# ATtiny85_and_DRV8830_Combo_--_v03.net
KiCad netlist of a schematic drawn in EAGLE
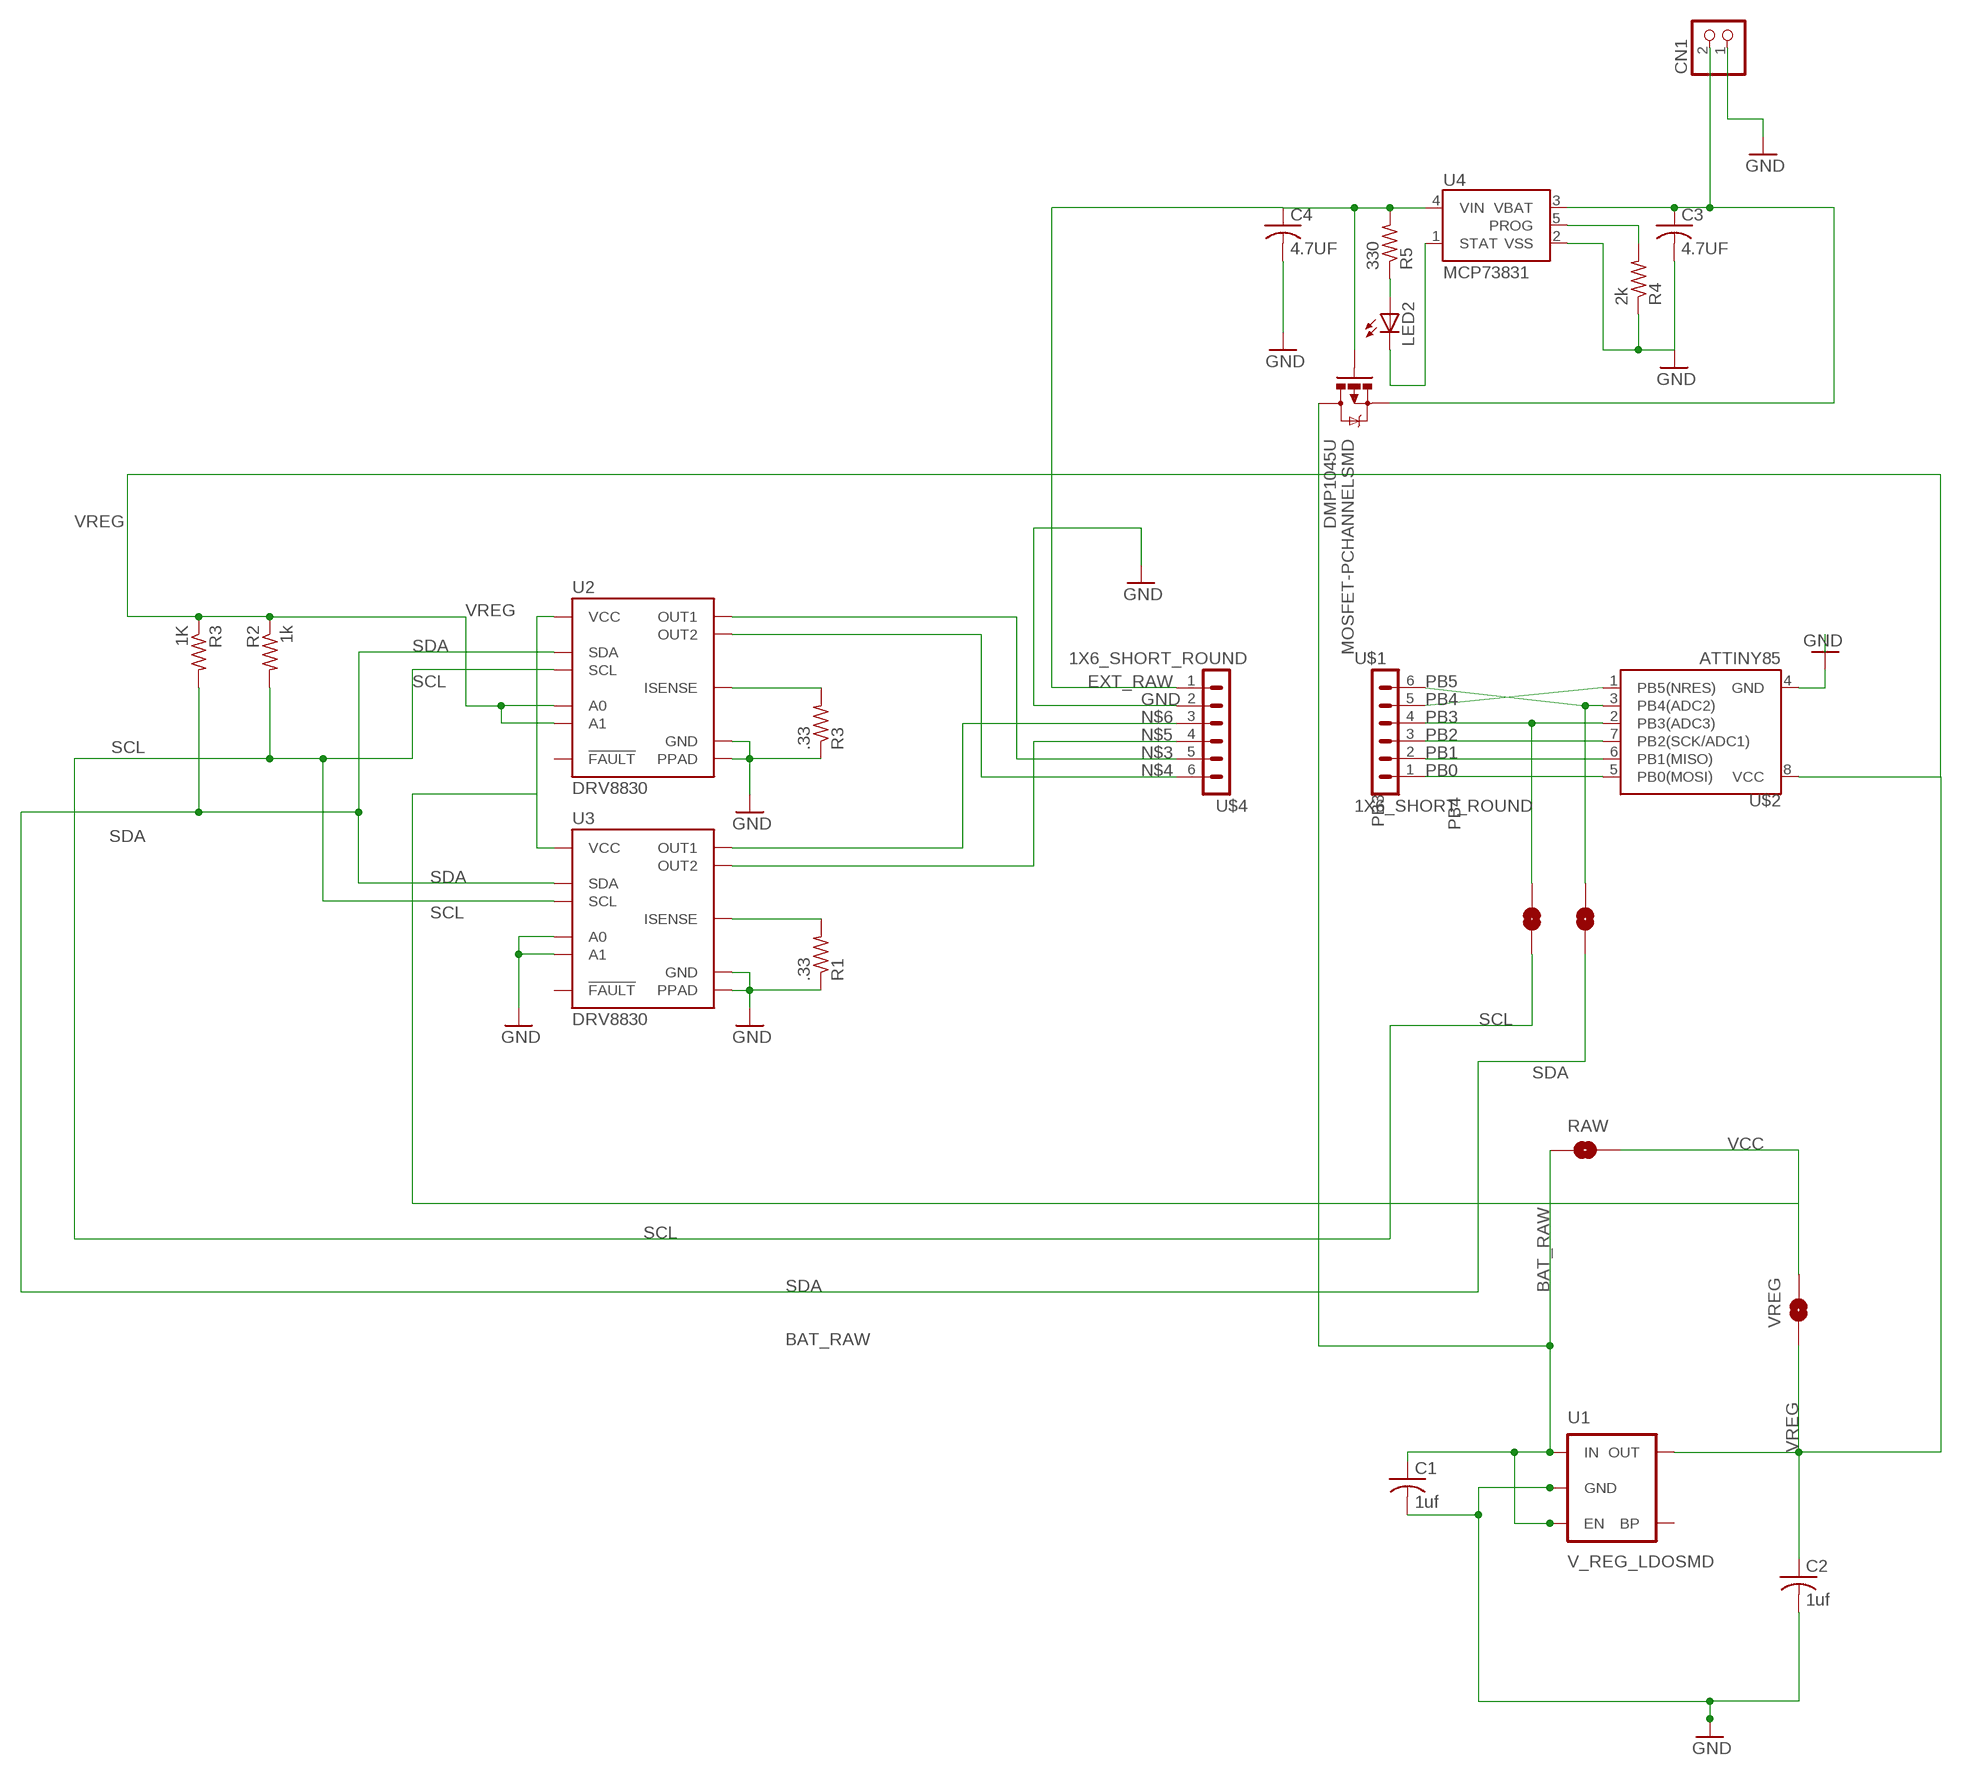
[diagram p0: schematic, sheet 1]

(export (version "E")
  (design (tool "Eeschema 10.0.6"))
  (components
    (comp (ref "1K")
      (value "R3")
      (footprint "eagle-import:R0402")
      (libsource (lib "eagle-import") (part "R-US_R0402"))
    )
    (comp (ref "C1")
      (value "1uf")
      (footprint "eagle-import:C0402")
      (libsource (lib "eagle-import") (part "C-USC0402"))
    )
    (comp (ref "C2")
      (value "1uf")
      (footprint "eagle-import:C0402")
      (libsource (lib "eagle-import") (part "C-USC0402"))
    )
    (comp (ref "C3")
      (value "4.7UF")
      (footprint "eagle-import:C0805K")
      (libsource (lib "eagle-import") (part "C-USC0805K"))
    )
    (comp (ref "C4")
      (value "4.7UF")
      (footprint "eagle-import:C0805K")
      (libsource (lib "eagle-import") (part "C-USC0805K"))
    )
    (comp (ref "CN1")
      (value "JST_2PIN-THM")
      (footprint "eagle-import:JST-PH-2-THM")
      (libsource (lib "eagle-import") (part "JST_2PIN-THM"))
    )
    (comp (ref "DMP1045U")
      (value "MOSFET-PCHANNELSMD")
      (footprint "eagle-import:SOT23-3")
      (libsource (lib "eagle-import") (part "MOSFET-PCHANNELSMD"))
    )
    (comp (ref "LED2")
      (value "LEDSML0603")
      (footprint "eagle-import:SML0603")
      (libsource (lib "eagle-import") (part "LEDSML0603"))
    )
    (comp (ref "R1")
      (value ".33")
      (footprint "eagle-import:R0402")
      (libsource (lib "eagle-import") (part "R-US_R0402"))
    )
    (comp (ref "R2")
      (value "1k")
      (footprint "eagle-import:R0402")
      (libsource (lib "eagle-import") (part "R-US_R0402"))
    )
    (comp (ref "R3")
      (value ".33")
      (footprint "eagle-import:R0402")
      (libsource (lib "eagle-import") (part "R-US_R0402"))
    )
    (comp (ref "R4")
      (value "2k")
      (footprint "eagle-import:R0402")
      (libsource (lib "eagle-import") (part "R-US_R0402"))
    )
    (comp (ref "R5")
      (value "330")
      (footprint "eagle-import:R0402")
      (libsource (lib "eagle-import") (part "R-US_R0402"))
    )
    (comp (ref "RAW")
      (value "SOLDERJUMPERNO")
      (footprint "eagle-import:SJ_2S-NO")
      (libsource (lib "eagle-import") (part "SOLDERJUMPERNO"))
    )
    (comp (ref "SJ6")
      (value "SOLDERJUMPERNO")
      (footprint "eagle-import:SJ_2S-NO")
      (libsource (lib "eagle-import") (part "SOLDERJUMPERNO"))
    )
    (comp (ref "SJ7")
      (value "SOLDERJUMPERNO")
      (footprint "eagle-import:SJ_2S-NO")
      (libsource (lib "eagle-import") (part "SOLDERJUMPERNO"))
    )
    (comp (ref "U$1")
      (value "1X6_SHORT_ROUND")
      (footprint "eagle-import:1X6_SHORT_ROUND")
      (libsource (lib "eagle-import") (part "1X6_SHORT_ROUND"))
    )
    (comp (ref "U$2")
      (value "ATTINY85")
      (footprint "eagle-import:SO08-EIAJ")
      (libsource (lib "eagle-import") (part "ATTINY45"))
    )
    (comp (ref "U$4")
      (value "1X6_SHORT_ROUND")
      (footprint "eagle-import:1X6_SHORT_ROUND")
      (libsource (lib "eagle-import") (part "1X6_SHORT_ROUND"))
    )
    (comp (ref "U1")
      (value "V_REG_LDOSMD")
      (footprint "eagle-import:SOT23-5")
      (libsource (lib "eagle-import") (part "V_REG_LDOSMD"))
    )
    (comp (ref "U2")
      (value "DRV8830")
      (footprint "eagle-import:MSOP-10-GNDPAD")
      (libsource (lib "eagle-import") (part "DRV8830"))
    )
    (comp (ref "U3")
      (value "DRV8830")
      (footprint "eagle-import:MSOP-10-GNDPAD")
      (libsource (lib "eagle-import") (part "DRV8830"))
    )
    (comp (ref "U4")
      (value "MCP73831")
      (footprint "eagle-import:SOT23-5")
      (libsource (lib "eagle-import") (part "MCP73831"))
    )
    (comp (ref "VREG")
      (value "SOLDERJUMPERNO")
      (footprint "eagle-import:SJ_2S-NO")
      (libsource (lib "eagle-import") (part "SOLDERJUMPERNO"))
    )
  )
  (nets
    (net (code "1") (name "/BAT_RAW") (class "Default")
      (node (ref "C1") (pin "1") (pinfunction "1_1") (pintype "passive"))
      (node (ref "DMP1045U") (pin "3") (pinfunction "D_3") (pintype "passive"))
      (node (ref "RAW") (pin "1") (pinfunction "1_1") (pintype "passive"))
      (node (ref "U1") (pin "1") (pinfunction "IN_1") (pintype "input"))
      (node (ref "U1") (pin "3") (pinfunction "EN_3") (pintype "input"))
    )
    (net (code "2") (name "/EXT_RAW") (class "Default")
      (node (ref "C4") (pin "1") (pinfunction "1_1") (pintype "passive"))
      (node (ref "DMP1045U") (pin "1") (pinfunction "G_1") (pintype "passive"))
      (node (ref "R5") (pin "2") (pinfunction "2_2") (pintype "passive"))
      (node (ref "U$4") (pin "1") (pinfunction "1_1") (pintype "passive"))
      (node (ref "U4") (pin "4") (pinfunction "VIN_4") (pintype "power_in"))
    )
    (net (code "3") (name "/N$3") (class "Default")
      (node (ref "U$4") (pin "5") (pinfunction "5_5") (pintype "passive"))
      (node (ref "U2") (pin "3") (pinfunction "OUT1_3") (pintype "power_in"))
    )
    (net (code "4") (name "/N$4") (class "Default")
      (node (ref "U$4") (pin "6") (pinfunction "6_6") (pintype "passive"))
      (node (ref "U2") (pin "1") (pinfunction "OUT2_1") (pintype "power_in"))
    )
    (net (code "5") (name "/N$5") (class "Default")
      (node (ref "U$4") (pin "4") (pinfunction "4_4") (pintype "passive"))
      (node (ref "U3") (pin "1") (pinfunction "OUT2_1") (pintype "power_in"))
    )
    (net (code "6") (name "/N$6") (class "Default")
      (node (ref "U$4") (pin "3") (pinfunction "3_3") (pintype "passive"))
      (node (ref "U3") (pin "3") (pinfunction "OUT1_3") (pintype "power_in"))
    )
    (net (code "7") (name "/PB0") (class "Default")
      (node (ref "U$1") (pin "1") (pinfunction "1_1") (pintype "passive"))
      (node (ref "U$2") (pin "5") (pinfunction "PB0(MOSI)_5") (pintype "bidirectional"))
    )
    (net (code "8") (name "/PB1") (class "Default")
      (node (ref "U$1") (pin "2") (pinfunction "2_2") (pintype "passive"))
      (node (ref "U$2") (pin "6") (pinfunction "PB1(MISO)_6") (pintype "bidirectional"))
    )
    (net (code "9") (name "/PB2") (class "Default")
      (node (ref "U$1") (pin "3") (pinfunction "3_3") (pintype "passive"))
      (node (ref "U$2") (pin "7") (pinfunction "PB2(SCK/ADC1)_7") (pintype "bidirectional"))
    )
    (net (code "10") (name "/PB3") (class "Default")
      (node (ref "SJ7") (pin "2") (pinfunction "2_2") (pintype "passive"))
      (node (ref "U$1") (pin "4") (pinfunction "4_4") (pintype "passive"))
      (node (ref "U$2") (pin "2") (pinfunction "PB3(ADC3)_2") (pintype "bidirectional"))
    )
    (net (code "11") (name "/PB4") (class "Default")
      (node (ref "SJ6") (pin "2") (pinfunction "2_2") (pintype "passive"))
      (node (ref "U$1") (pin "6") (pinfunction "6_6") (pintype "passive"))
      (node (ref "U$2") (pin "3") (pinfunction "PB4(ADC2)_3") (pintype "bidirectional"))
    )
    (net (code "12") (name "/PB5") (class "Default")
      (node (ref "U$1") (pin "5") (pinfunction "5_5") (pintype "passive"))
      (node (ref "U$2") (pin "1") (pinfunction "PB5(NRES)_1") (pintype "bidirectional"))
    )
    (net (code "13") (name "/SCL") (class "Default")
      (node (ref "R2") (pin "2") (pinfunction "2_2") (pintype "passive"))
      (node (ref "SJ7") (pin "1") (pinfunction "1_1") (pintype "passive"))
      (node (ref "U2") (pin "10") (pinfunction "SCL_10") (pintype "input"))
      (node (ref "U3") (pin "10") (pinfunction "SCL_10") (pintype "input"))
    )
    (net (code "14") (name "/SDA") (class "Default")
      (node (ref "1K") (pin "2") (pinfunction "2_2") (pintype "passive"))
      (node (ref "SJ6") (pin "1") (pinfunction "1_1") (pintype "passive"))
      (node (ref "U2") (pin "9") (pinfunction "SDA_9") (pintype "bidirectional"))
      (node (ref "U3") (pin "9") (pinfunction "SDA_9") (pintype "bidirectional"))
    )
    (net (code "15") (name "/VCC") (class "Default")
      (node (ref "RAW") (pin "2") (pinfunction "2_2") (pintype "passive"))
      (node (ref "U2") (pin "4") (pinfunction "VCC_4") (pintype "power_in"))
      (node (ref "U3") (pin "4") (pinfunction "VCC_4") (pintype "power_in"))
      (node (ref "VREG") (pin "2") (pinfunction "2_2") (pintype "passive"))
    )
    (net (code "16") (name "/VREG") (class "Default")
      (node (ref "1K") (pin "1") (pinfunction "1_1") (pintype "passive"))
      (node (ref "C2") (pin "1") (pinfunction "1_1") (pintype "passive"))
      (node (ref "R2") (pin "1") (pinfunction "1_1") (pintype "passive"))
      (node (ref "U$2") (pin "8") (pinfunction "VCC_8") (pintype "bidirectional"))
      (node (ref "U1") (pin "5") (pinfunction "OUT_5") (pintype "passive"))
      (node (ref "U2") (pin "7") (pinfunction "A0_7") (pintype "input"))
      (node (ref "U2") (pin "8") (pinfunction "A1_8") (pintype "input"))
      (node (ref "VREG") (pin "1") (pinfunction "1_1") (pintype "passive"))
    )
    (net (code "17") (name "GND") (class "Default")
      (node (ref "C1") (pin "2") (pinfunction "2_2") (pintype "passive"))
      (node (ref "C2") (pin "2") (pinfunction "2_2") (pintype "passive"))
      (node (ref "C3") (pin "2") (pinfunction "2_2") (pintype "passive"))
      (node (ref "C4") (pin "2") (pinfunction "2_2") (pintype "passive"))
      (node (ref "CN1") (pin "1") (pinfunction "2_1") (pintype "passive"))
      (node (ref "R1") (pin "1") (pinfunction "1_1") (pintype "passive"))
      (node (ref "R3") (pin "1") (pinfunction "1_1") (pintype "passive"))
      (node (ref "R4") (pin "1") (pinfunction "1_1") (pintype "passive"))
      (node (ref "U$2") (pin "4") (pinfunction "GND_4") (pintype "bidirectional"))
      (node (ref "U$4") (pin "2") (pinfunction "2_2") (pintype "passive"))
      (node (ref "U1") (pin "2") (pinfunction "GND_2") (pintype "input"))
      (node (ref "U2") (pin "5") (pinfunction "GND_5") (pintype "power_in"))
      (node (ref "U2") (pin "GND") (pinfunction "PPAD_GND") (pintype "power_in"))
      (node (ref "U3") (pin "5") (pinfunction "GND_5") (pintype "power_in"))
      (node (ref "U3") (pin "7") (pinfunction "A0_7") (pintype "input"))
      (node (ref "U3") (pin "8") (pinfunction "A1_8") (pintype "input"))
      (node (ref "U3") (pin "GND") (pinfunction "PPAD_GND") (pintype "power_in"))
      (node (ref "U4") (pin "2") (pinfunction "VSS_2") (pintype "power_in"))
    )
    (net (code "18") (name "Net-(CN1-1)") (class "Default")
      (node (ref "C3") (pin "1") (pinfunction "1_1") (pintype "passive"))
      (node (ref "CN1") (pin "2") (pinfunction "1_2") (pintype "passive"))
      (node (ref "DMP1045U") (pin "2") (pinfunction "S_2") (pintype "passive"))
      (node (ref "U4") (pin "3") (pinfunction "VBAT_3") (pintype "power_in"))
    )
    (net (code "19") (name "Net-(LED2-PadA)") (class "Default")
      (node (ref "LED2") (pin "A") (pinfunction "A_A") (pintype "passive"))
      (node (ref "R5") (pin "1") (pinfunction "1_1") (pintype "passive"))
    )
    (net (code "20") (name "Net-(U2-ISENSE)") (class "Default")
      (node (ref "R3") (pin "2") (pinfunction "2_2") (pintype "passive"))
      (node (ref "U2") (pin "2") (pinfunction "ISENSE_2") (pintype "bidirectional"))
    )
    (net (code "21") (name "Net-(U3-ISENSE)") (class "Default")
      (node (ref "R1") (pin "2") (pinfunction "2_2") (pintype "passive"))
      (node (ref "U3") (pin "2") (pinfunction "ISENSE_2") (pintype "bidirectional"))
    )
    (net (code "22") (name "Net-(U4-PROG)") (class "Default")
      (node (ref "R4") (pin "2") (pinfunction "2_2") (pintype "passive"))
      (node (ref "U4") (pin "5") (pinfunction "PROG_5") (pintype "input"))
    )
    (net (code "23") (name "Net-(U4-STAT)") (class "Default")
      (node (ref "LED2") (pin "C") (pinfunction "C_C") (pintype "passive"))
      (node (ref "U4") (pin "1") (pinfunction "STAT_1") (pintype "output"))
    )
    (net (code "24") (name "unconnected-(U1-BP-Pad4)") (class "Default")
      (node (ref "U1") (pin "4") (pinfunction "BP_4") (pintype "input"))
    )
    (net (code "25") (name "unconnected-(U2-~{FAULT}-Pad6)") (class "Default")
      (node (ref "U2") (pin "6") (pinfunction "~{FAULT}_6") (pintype "output"))
    )
    (net (code "26") (name "unconnected-(U3-~{FAULT}-Pad6)") (class "Default")
      (node (ref "U3") (pin "6") (pinfunction "~{FAULT}_6") (pintype "output"))
    )
  )
)
